# MM-Esp32S3.net
KiCad netlist of a schematic drawn in Altium Designer
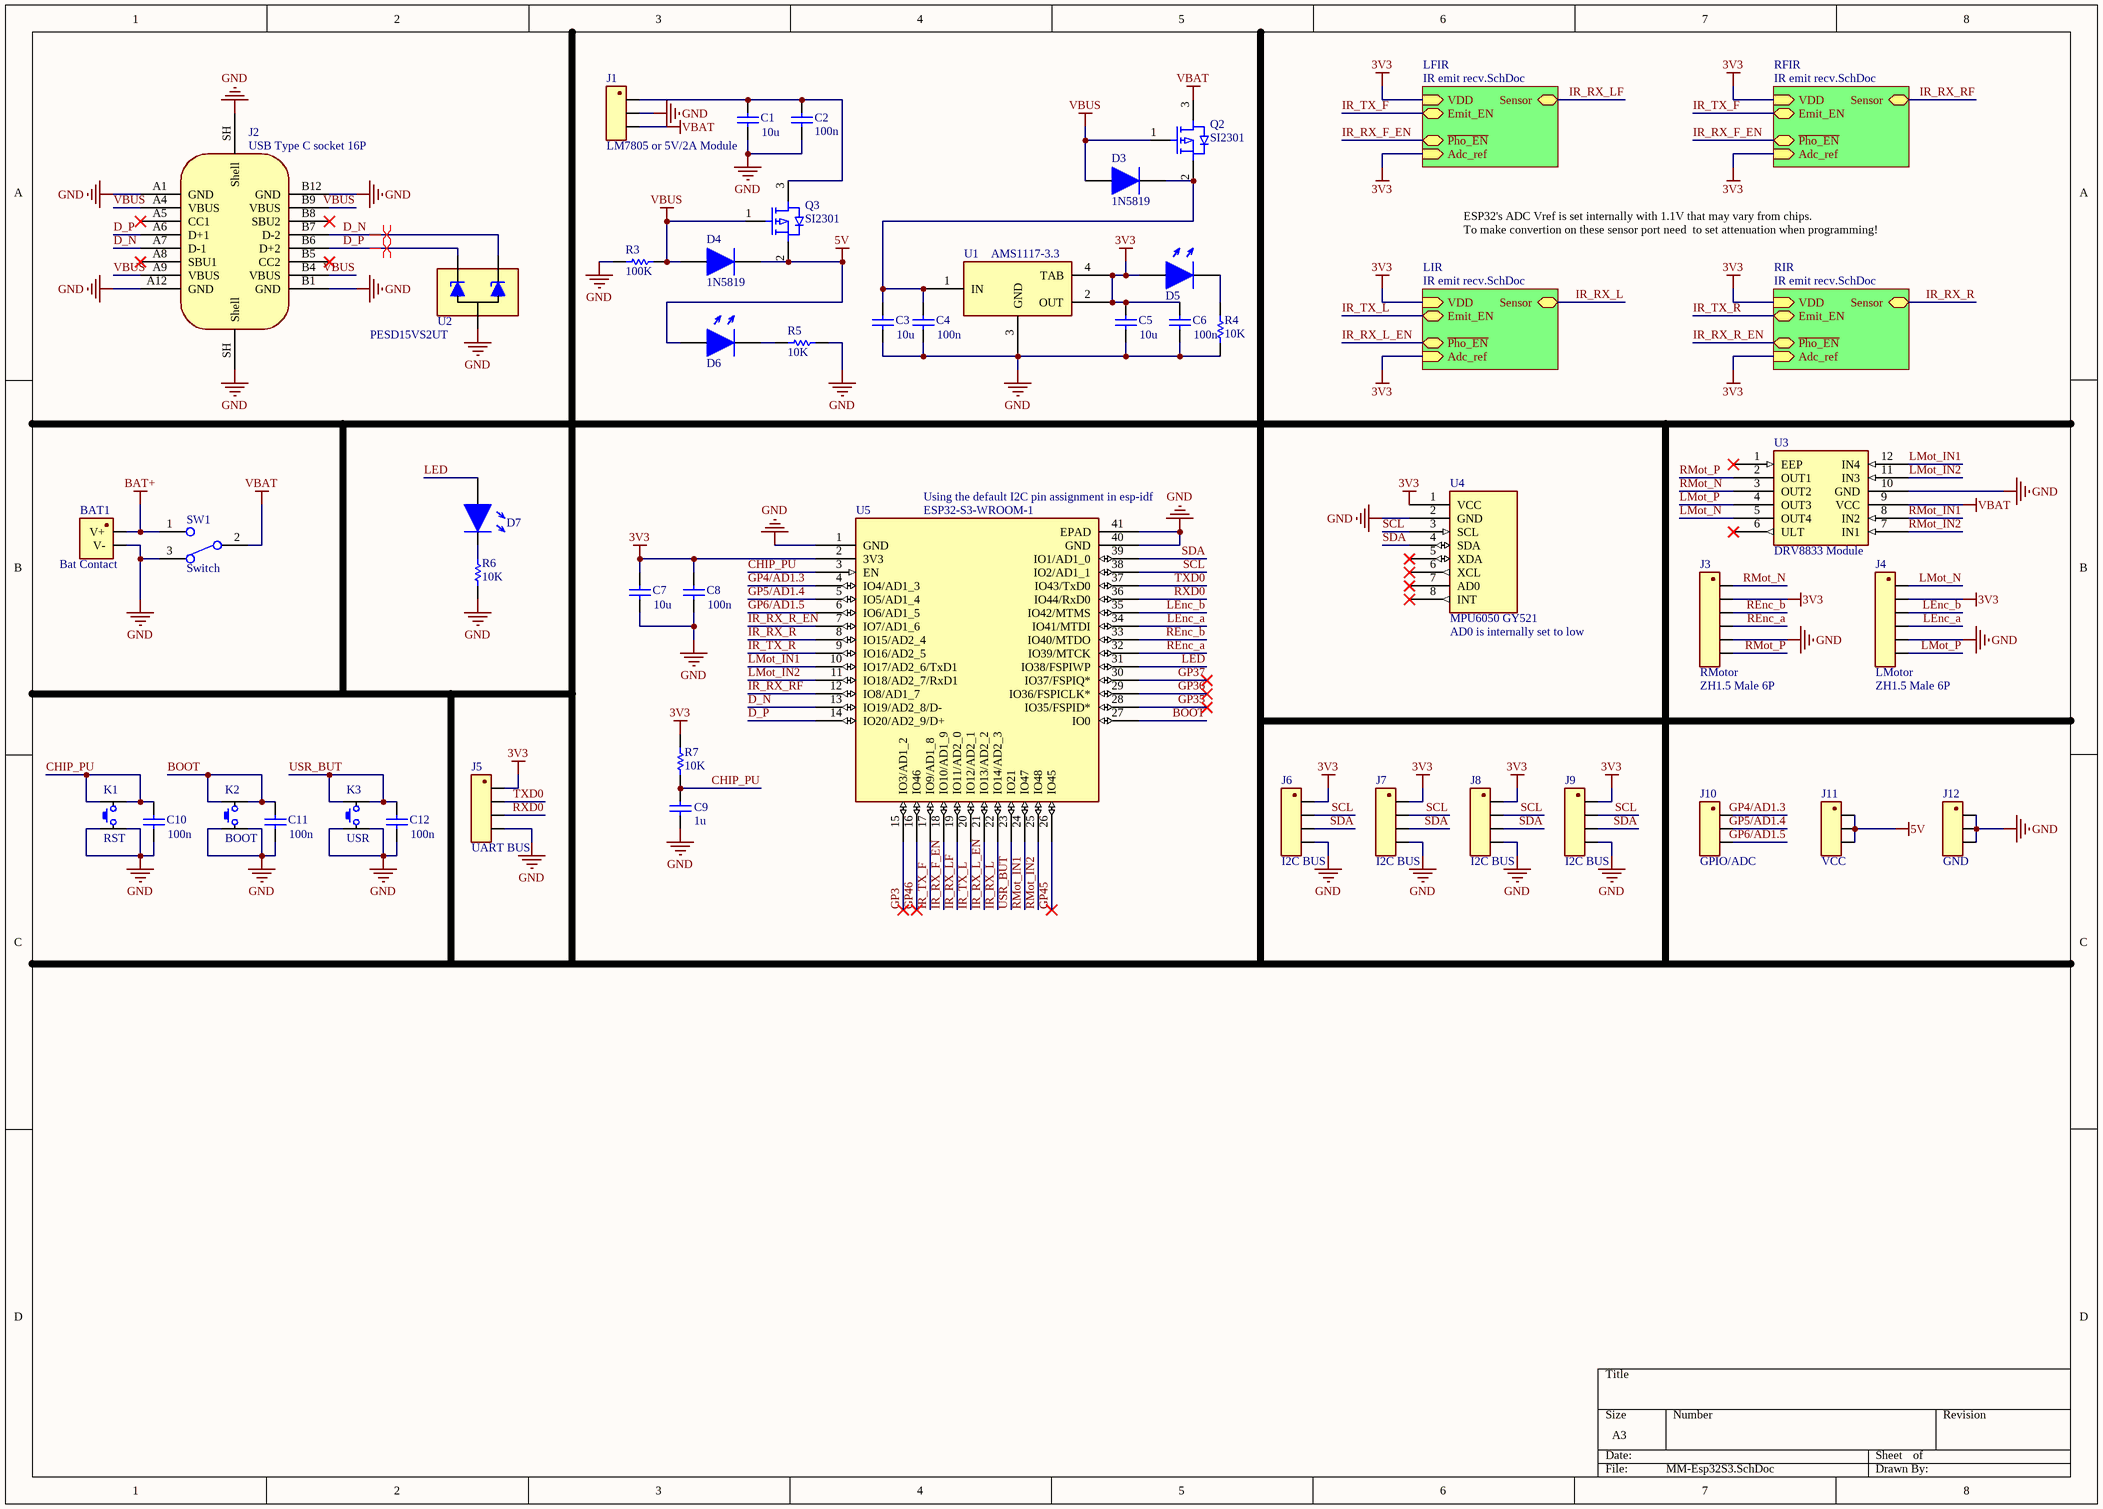
[diagram p0: MM-Esp32S3.SchDoc]

(export (version "E")
  (design (tool "Eeschema 10.0.6"))
  (components
    (comp (ref "BAT1")
      (value "Bat Contact")
      (footprint "9V BAT SNAP-ON 2 CONTACTS MF")
      (libsource (lib "My_Library") (part "Bat Contact"))
    )
    (comp (ref "C1")
      (value "10u")
      (footprint "0805 Cap")
      (description "无极电容")
      (fields (field (name "Comment") "Cap"))
      (libsource (lib "My_Library") (part "Cap"))
    )
    (comp (ref "C2")
      (value "100n")
      (footprint "0805 Cap")
      (description "无极电容")
      (fields (field (name "Comment") "Cap"))
      (libsource (lib "My_Library") (part "Cap"))
    )
    (comp (ref "C3")
      (value "10u")
      (footprint "0805 Cap")
      (description "无极电容")
      (fields (field (name "Comment") "Cap"))
      (libsource (lib "My_Library") (part "Cap"))
    )
    (comp (ref "C4")
      (value "100n")
      (footprint "0805 Cap")
      (description "无极电容")
      (fields (field (name "Comment") "Cap"))
      (libsource (lib "My_Library") (part "Cap"))
    )
    (comp (ref "C5")
      (value "10u")
      (footprint "0805 Cap")
      (description "无极电容")
      (fields (field (name "Comment") "Cap"))
      (libsource (lib "My_Library") (part "Cap"))
    )
    (comp (ref "C6")
      (value "100n")
      (footprint "0805 Cap")
      (description "无极电容")
      (fields (field (name "Comment") "Cap"))
      (libsource (lib "My_Library") (part "Cap"))
    )
    (comp (ref "C7")
      (value "10u")
      (footprint "0805 Cap")
      (description "无极电容")
      (fields (field (name "Comment") "Cap"))
      (libsource (lib "My_Library") (part "Cap"))
    )
    (comp (ref "C8")
      (value "100n")
      (footprint "0805 Cap")
      (description "无极电容")
      (fields (field (name "Comment") "Cap"))
      (libsource (lib "My_Library") (part "Cap"))
    )
    (comp (ref "C9")
      (value "1u")
      (footprint "0805 Cap")
      (description "无极电容")
      (fields (field (name "Comment") "Cap"))
      (libsource (lib "My_Library") (part "Cap"))
    )
    (comp (ref "C10")
      (value "100n")
      (footprint "0805 Cap")
      (description "无极电容")
      (fields (field (name "Comment") "Cap"))
      (libsource (lib "My_Library") (part "Cap"))
    )
    (comp (ref "C11")
      (value "100n")
      (footprint "0805 Cap")
      (description "无极电容")
      (fields (field (name "Comment") "Cap"))
      (libsource (lib "My_Library") (part "Cap"))
    )
    (comp (ref "C12")
      (value "100n")
      (footprint "0805 Cap")
      (description "无极电容")
      (fields (field (name "Comment") "Cap"))
      (libsource (lib "My_Library") (part "Cap"))
    )
    (comp (ref "D3") (value "1N5819") (footprint "SOD323 0805") (libsource (lib "My_Library") (part "Diode")))
    (comp (ref "D4") (value "1N5819") (footprint "SOD323 0805") (libsource (lib "My_Library") (part "Diode")))
    (comp (ref "D5")
      (value "LED")
      (footprint "LED 3mm")
      (description "发光二极管")
      (libsource (lib "My_Library") (part "LED"))
    )
    (comp (ref "D6")
      (value "LED")
      (footprint "LED 3mm")
      (description "发光二极管")
      (libsource (lib "My_Library") (part "LED"))
    )
    (comp (ref "D7")
      (value "LED")
      (footprint "LED 3mm")
      (description "发光二极管")
      (libsource (lib "My_Library") (part "LED"))
    )
    (comp (ref "J1")
      (value "LM7805 or 5V/2A Module")
      (footprint "Header 3Pins Female DIP")
      (libsource (lib "My_Library") (part "Header 3pin"))
    )
    (comp (ref "J2")
      (value "USB Type C socket 16P")
      (footprint "USB Type C 16P Through hole")
      (description "USB Type C母座 16P")
      (libsource (lib "My_Library") (part "USB Type C socket 16P"))
    )
    (comp (ref "J3")
      (value "RMotor")
      (footprint "ZH1.5 6PINS DIP")
      (fields (field (name "SIZE") "ZH1.5 Male 6P"))
      (libsource (lib "My_Library") (part "Header 6pin"))
    )
    (comp (ref "J4")
      (value "LMotor")
      (footprint "ZH1.5 6PINS DIP")
      (fields (field (name "SIZE") "ZH1.5 Male 6P"))
      (libsource (lib "My_Library") (part "Header 6pin"))
    )
    (comp (ref "J5")
      (value "UART BUS")
      (footprint "Header 4Pins DIP")
      (libsource (lib "My_Library") (part "Header 4pin"))
    )
    (comp (ref "J6")
      (value "I2C BUS")
      (footprint "Header 4Pins DIP")
      (libsource (lib "My_Library") (part "Header 4pin"))
    )
    (comp (ref "J7")
      (value "I2C BUS")
      (footprint "Header 4Pins DIP")
      (libsource (lib "My_Library") (part "Header 4pin"))
    )
    (comp (ref "J8")
      (value "I2C BUS")
      (footprint "Header 4Pins DIP")
      (libsource (lib "My_Library") (part "Header 4pin"))
    )
    (comp (ref "J9")
      (value "I2C BUS")
      (footprint "Header 4Pins DIP")
      (libsource (lib "My_Library") (part "Header 4pin"))
    )
    (comp (ref "J10")
      (value "GPIO/ADC")
      (footprint "Header 3Pins DIP")
      (libsource (lib "My_Library") (part "Header 3pin"))
    )
    (comp (ref "J11")
      (value "VCC")
      (footprint "Header 3Pins DIP")
      (libsource (lib "My_Library") (part "Header 3pin"))
    )
    (comp (ref "J12")
      (value "GND")
      (footprint "Header 3Pins DIP")
      (libsource (lib "My_Library") (part "Header 3pin"))
    )
    (comp (ref "K1")
      (value "RST")
      (footprint "BUTTON TH 6*6*5")
      (description "按键开关")
      (libsource (lib "My_Library") (part "Button"))
    )
    (comp (ref "K2")
      (value "BOOT")
      (footprint "BUTTON TH 6*6*5")
      (description "按键开关")
      (libsource (lib "My_Library") (part "Button"))
    )
    (comp (ref "K3")
      (value "USR")
      (footprint "BUTTON TH 6*6*5")
      (description "按键开关")
      (libsource (lib "My_Library") (part "Button"))
    )
    (comp (ref "Q2") (value "SI2301") (footprint "SOT23-3") (libsource (lib "My_Library") (part "PMOS")))
    (comp (ref "Q3") (value "SI2301") (footprint "SOT23-3") (libsource (lib "My_Library") (part "PMOS")))
    (comp (ref "R3")
      (value "100K")
      (footprint "0805 R/L")
      (fields (field (name "Comment") "Res"))
      (libsource (lib "My_Library") (part "Res"))
    )
    (comp (ref "R4")
      (value "10K")
      (footprint "0805 R/L")
      (fields (field (name "Comment") "Res"))
      (libsource (lib "My_Library") (part "Res"))
    )
    (comp (ref "R5")
      (value "10K")
      (footprint "0805 R/L")
      (fields (field (name "Comment") "Res"))
      (libsource (lib "My_Library") (part "Res"))
    )
    (comp (ref "R6")
      (value "10K")
      (footprint "0805 R/L")
      (fields (field (name "Comment") "Res"))
      (libsource (lib "My_Library") (part "Res"))
    )
    (comp (ref "R7")
      (value "10K")
      (footprint "0805 R/L")
      (fields (field (name "Comment") "Res"))
      (libsource (lib "My_Library") (part "Res"))
    )
    (comp (ref "SW1")
      (value "Switch")
      (footprint "Slide switch")
      (description "开关 拨动开关 滑动开关")
      (libsource (lib "My_Library") (part "Switch"))
    )
    (comp (ref "U1")
      (value "AMS1117-3.3")
      (footprint "SOT-223")
      (libsource (lib "My_Library") (part "AMS1117"))
    )
    (comp (ref "U2")
      (value "PESD15VS2UT")
      (footprint "SOT23-3")
      (description "静电放电(ESD)保护器件")
      (libsource (lib "My_Library") (part "PESD15VS2UT"))
    )
    (comp (ref "U3")
      (value "DRV8833 Module")
      (footprint "DRV8833 MODULE")
      (description "DRV8833两路电机驱动模块\r\nhttps://detail.tmall.com/item.htm?id=543193414673")
      (libsource (lib "My_Library") (part "DRV8833 Module"))
    )
    (comp (ref "U4")
      (value "MPU6050 GY521")
      (footprint "MPU6050 Module")
      (description "淘宝上最常用的8针脚MPU6050")
      (libsource (lib "My_Library") (part "MPU6050 GY521"))
    )
    (comp (ref "U5")
      (value "ESP32-S3-WROOM-1")
      (footprint "ESP32-WROOM")
      (description "乐鑫ESP32S3Wroom模组\r\n内置芯片为ESP32-S3R8的模组中,*管脚只能用于连至内部的OSPI PSRAM")
      (libsource (lib "My_Library") (part "ESP32-S3-WROOM-1"))
    )
  )
  (nets
    (net (code "1") (name "/BOOT") (class "Default")
      (node (ref "C11") (pin "2") (pintype "passive"))
      (node (ref "K2") (pin "1") (pintype "passive"))
      (node (ref "K2") (pin "2") (pintype "passive"))
      (node (ref "U5") (pin "27") (pinfunction "IO0_27") (pintype "bidirectional"))
    )
    (net (code "2") (name "/CHIP_PU") (class "Default")
      (node (ref "C10") (pin "2") (pintype "passive"))
      (node (ref "C9") (pin "2") (pintype "passive"))
      (node (ref "K1") (pin "1") (pintype "passive"))
      (node (ref "K1") (pin "2") (pintype "passive"))
      (node (ref "R7") (pin "2") (pintype "passive"))
      (node (ref "U5") (pin "3") (pinfunction "EN_3") (pintype "input"))
    )
    (net (code "3") (name "/D_N") (class "Default")
      (node (ref "J2") (pin "A7") (pinfunction "D-1_A7") (pintype "passive"))
      (node (ref "J2") (pin "B7") (pinfunction "D-2_B7") (pintype "passive"))
      (node (ref "U2") (pin "1") (pintype "passive"))
      (node (ref "U5") (pin "13") (pinfunction "IO19/AD2_8/D-_13") (pintype "bidirectional"))
    )
    (net (code "4") (name "/D_P") (class "Default")
      (node (ref "J2") (pin "A6") (pinfunction "D+1_A6") (pintype "passive"))
      (node (ref "J2") (pin "B6") (pinfunction "D+2_B6") (pintype "passive"))
      (node (ref "U2") (pin "2") (pintype "passive"))
      (node (ref "U5") (pin "14") (pinfunction "IO20/AD2_9/D+_14") (pintype "bidirectional"))
    )
    (net (code "5") (name "/GP3") (class "Default")
      (node (ref "U5") (pin "15") (pinfunction "IO3/AD1_2_15") (pintype "bidirectional+no_connect"))
    )
    (net (code "6") (name "/GP4{slash}AD1.3") (class "Default")
      (node (ref "J10") (pin "1") (pintype "passive"))
      (node (ref "U5") (pin "4") (pinfunction "IO4/AD1_3_4") (pintype "bidirectional"))
    )
    (net (code "7") (name "/GP5{slash}AD1.4") (class "Default")
      (node (ref "J10") (pin "2") (pintype "passive"))
      (node (ref "U5") (pin "5") (pinfunction "IO5/AD1_4_5") (pintype "bidirectional"))
    )
    (net (code "8") (name "/GP6{slash}AD1.5") (class "Default")
      (node (ref "J10") (pin "3") (pintype "passive"))
      (node (ref "U5") (pin "6") (pinfunction "IO6/AD1_5_6") (pintype "bidirectional"))
    )
    (net (code "9") (name "/GP35") (class "Default")
      (node (ref "U5") (pin "28") (pinfunction "IO35/FSPID*_28") (pintype "bidirectional+no_connect"))
    )
    (net (code "10") (name "/GP36") (class "Default")
      (node (ref "U5") (pin "29") (pinfunction "IO36/FSPICLK*_29") (pintype "bidirectional+no_connect"))
    )
    (net (code "11") (name "/GP37") (class "Default")
      (node (ref "U5") (pin "30") (pinfunction "IO37/FSPIQ*_30") (pintype "bidirectional+no_connect"))
    )
    (net (code "12") (name "/GP45") (class "Default")
      (node (ref "U5") (pin "26") (pinfunction "IO45_26") (pintype "bidirectional+no_connect"))
    )
    (net (code "13") (name "/GP46") (class "Default")
      (node (ref "U5") (pin "16") (pinfunction "IO46_16") (pintype "bidirectional+no_connect"))
    )
    (net (code "14") (name "/IR_RX_F_EN") (class "Default")
      (node (ref "U5") (pin "18") (pinfunction "IO10/AD1_9_18") (pintype "bidirectional"))
    )
    (net (code "15") (name "/IR_RX_L") (class "Default")
      (node (ref "U5") (pin "22") (pinfunction "IO14/AD2_3_22") (pintype "bidirectional"))
    )
    (net (code "16") (name "/IR_RX_LF") (class "Default")
      (node (ref "U5") (pin "19") (pinfunction "IO11/AD2_0_19") (pintype "bidirectional"))
    )
    (net (code "17") (name "/IR_RX_L_EN") (class "Default")
      (node (ref "U5") (pin "21") (pinfunction "IO13/AD2_2_21") (pintype "bidirectional"))
    )
    (net (code "18") (name "/IR_RX_R") (class "Default")
      (node (ref "U5") (pin "8") (pinfunction "IO15/AD2_4_8") (pintype "bidirectional"))
    )
    (net (code "19") (name "/IR_RX_RF") (class "Default")
      (node (ref "U5") (pin "12") (pinfunction "IO8/AD1_7_12") (pintype "bidirectional"))
    )
    (net (code "20") (name "/IR_RX_R_EN") (class "Default")
      (node (ref "U5") (pin "7") (pinfunction "IO7/AD1_6_7") (pintype "bidirectional"))
    )
    (net (code "21") (name "/IR_TX_F") (class "Default")
      (node (ref "U5") (pin "17") (pinfunction "IO9/AD1_8_17") (pintype "bidirectional"))
    )
    (net (code "22") (name "/IR_TX_L") (class "Default")
      (node (ref "U5") (pin "20") (pinfunction "IO12/AD2_1_20") (pintype "bidirectional"))
    )
    (net (code "23") (name "/IR_TX_R") (class "Default")
      (node (ref "U5") (pin "9") (pinfunction "IO16/AD2_5_9") (pintype "bidirectional"))
    )
    (net (code "24") (name "/LED") (class "Default")
      (node (ref "D7") (pin "2") (pintype "passive"))
      (node (ref "U5") (pin "31") (pinfunction "IO38/FSPIWP_31") (pintype "bidirectional"))
    )
    (net (code "25") (name "/LEnc_a") (class "Default")
      (node (ref "J4") (pin "4") (pintype "passive"))
      (node (ref "U5") (pin "34") (pinfunction "IO41/MTDI_34") (pintype "bidirectional"))
    )
    (net (code "26") (name "/LEnc_b") (class "Default")
      (node (ref "J4") (pin "3") (pintype "passive"))
      (node (ref "U5") (pin "35") (pinfunction "IO42/MTMS_35") (pintype "bidirectional"))
    )
    (net (code "27") (name "/LMot_IN1") (class "Default")
      (node (ref "U3") (pin "12") (pinfunction "IN4_12") (pintype "input"))
      (node (ref "U5") (pin "10") (pinfunction "IO17/AD2_6/TxD1_10") (pintype "bidirectional"))
    )
    (net (code "28") (name "/LMot_IN2") (class "Default")
      (node (ref "U3") (pin "11") (pinfunction "IN3_11") (pintype "input"))
      (node (ref "U5") (pin "11") (pinfunction "IO18/AD2_7/RxD1_11") (pintype "bidirectional"))
    )
    (net (code "29") (name "/LMot_N") (class "Default")
      (node (ref "J4") (pin "1") (pintype "passive"))
      (node (ref "U3") (pin "5") (pinfunction "OUT4_5") (pintype "passive"))
    )
    (net (code "30") (name "/LMot_P") (class "Default")
      (node (ref "J4") (pin "6") (pintype "passive"))
      (node (ref "U3") (pin "4") (pinfunction "OUT3_4") (pintype "passive"))
    )
    (net (code "31") (name "/REnc_a") (class "Default")
      (node (ref "J3") (pin "4") (pintype "passive"))
      (node (ref "U5") (pin "32") (pinfunction "IO39/MTCK_32") (pintype "bidirectional"))
    )
    (net (code "32") (name "/REnc_b") (class "Default")
      (node (ref "J3") (pin "3") (pintype "passive"))
      (node (ref "U5") (pin "33") (pinfunction "IO40/MTDO_33") (pintype "bidirectional"))
    )
    (net (code "33") (name "/RMot_IN1") (class "Default")
      (node (ref "U3") (pin "8") (pinfunction "IN2_8") (pintype "input"))
      (node (ref "U5") (pin "24") (pinfunction "IO47_24") (pintype "bidirectional"))
    )
    (net (code "34") (name "/RMot_IN2") (class "Default")
      (node (ref "U3") (pin "7") (pinfunction "IN1_7") (pintype "input"))
      (node (ref "U5") (pin "25") (pinfunction "IO48_25") (pintype "bidirectional"))
    )
    (net (code "35") (name "/RMot_N") (class "Default")
      (node (ref "J3") (pin "1") (pintype "passive"))
      (node (ref "U3") (pin "3") (pinfunction "OUT2_3") (pintype "passive"))
    )
    (net (code "36") (name "/RMot_P") (class "Default")
      (node (ref "J3") (pin "6") (pintype "passive"))
      (node (ref "U3") (pin "2") (pinfunction "OUT1_2") (pintype "power_in"))
    )
    (net (code "37") (name "/RXD0") (class "Default")
      (node (ref "J5") (pin "3") (pintype "passive"))
      (node (ref "U5") (pin "36") (pinfunction "IO44/RxD0_36") (pintype "bidirectional"))
    )
    (net (code "38") (name "/SCL") (class "Default")
      (node (ref "J6") (pin "2") (pintype "passive"))
      (node (ref "J7") (pin "2") (pintype "passive"))
      (node (ref "J8") (pin "2") (pintype "passive"))
      (node (ref "J9") (pin "2") (pintype "passive"))
      (node (ref "U4") (pin "3") (pinfunction "SCL_3") (pintype "input"))
      (node (ref "U5") (pin "38") (pinfunction "IO2/AD1_1_38") (pintype "bidirectional"))
    )
    (net (code "39") (name "/SDA") (class "Default")
      (node (ref "J6") (pin "3") (pintype "passive"))
      (node (ref "J7") (pin "3") (pintype "passive"))
      (node (ref "J8") (pin "3") (pintype "passive"))
      (node (ref "J9") (pin "3") (pintype "passive"))
      (node (ref "U4") (pin "4") (pinfunction "SDA_4") (pintype "bidirectional"))
      (node (ref "U5") (pin "39") (pinfunction "IO1/AD1_0_39") (pintype "bidirectional"))
    )
    (net (code "40") (name "/TXD0") (class "Default")
      (node (ref "J5") (pin "2") (pintype "passive"))
      (node (ref "U5") (pin "37") (pinfunction "IO43/TxD0_37") (pintype "bidirectional"))
    )
    (net (code "41") (name "/USR_BUT") (class "Default")
      (node (ref "C12") (pin "2") (pintype "passive"))
      (node (ref "K3") (pin "1") (pintype "passive"))
      (node (ref "K3") (pin "2") (pintype "passive"))
      (node (ref "U5") (pin "23") (pinfunction "IO21_23") (pintype "bidirectional"))
    )
    (net (code "42") (name "3V3") (class "Default")
      (node (ref "C5") (pin "2") (pintype "passive"))
      (node (ref "C6") (pin "2") (pintype "passive"))
      (node (ref "C7") (pin "2") (pintype "passive"))
      (node (ref "C8") (pin "2") (pintype "passive"))
      (node (ref "D5") (pin "2") (pintype "passive"))
      (node (ref "J3") (pin "2") (pintype "passive"))
      (node (ref "J4") (pin "2") (pintype "passive"))
      (node (ref "J5") (pin "1") (pintype "passive"))
      (node (ref "J6") (pin "1") (pintype "passive"))
      (node (ref "J7") (pin "1") (pintype "passive"))
      (node (ref "J8") (pin "1") (pintype "passive"))
      (node (ref "J9") (pin "1") (pintype "passive"))
      (node (ref "R7") (pin "1") (pintype "passive"))
      (node (ref "U1") (pin "2") (pinfunction "OUT_2") (pintype "power_in"))
      (node (ref "U1") (pin "4") (pinfunction "TAB_4") (pintype "passive"))
      (node (ref "U4") (pin "1") (pinfunction "VCC_1") (pintype "power_in"))
      (node (ref "U5") (pin "2") (pinfunction "3V3_2") (pintype "power_in"))
    )
    (net (code "43") (name "5V") (class "Default")
      (node (ref "D4") (pin "2") (pintype "passive"))
      (node (ref "D6") (pin "2") (pintype "passive"))
      (node (ref "J11") (pin "1") (pintype "passive"))
      (node (ref "J11") (pin "2") (pintype "passive"))
      (node (ref "J11") (pin "3") (pintype "passive"))
      (node (ref "Q3") (pin "2") (pinfunction "S_2") (pintype "passive"))
    )
    (net (code "44") (name "BAT+") (class "Default")
      (node (ref "BAT1") (pin "1") (pinfunction "V+_1") (pintype "passive"))
      (node (ref "SW1") (pin "1") (pintype "passive"))
    )
    (net (code "45") (name "GND") (class "Default")
      (node (ref "BAT1") (pin "2") (pinfunction "V-_2") (pintype "passive"))
      (node (ref "C1") (pin "1") (pintype "passive"))
      (node (ref "C10") (pin "1") (pintype "passive"))
      (node (ref "C11") (pin "1") (pintype "passive"))
      (node (ref "C12") (pin "1") (pintype "passive"))
      (node (ref "C2") (pin "1") (pintype "passive"))
      (node (ref "C3") (pin "1") (pintype "passive"))
      (node (ref "C4") (pin "1") (pintype "passive"))
      (node (ref "C5") (pin "1") (pintype "passive"))
      (node (ref "C6") (pin "1") (pintype "passive"))
      (node (ref "C7") (pin "1") (pintype "passive"))
      (node (ref "C8") (pin "1") (pintype "passive"))
      (node (ref "C9") (pin "1") (pintype "passive"))
      (node (ref "J1") (pin "2") (pintype "passive"))
      (node (ref "J12") (pin "1") (pintype "passive"))
      (node (ref "J12") (pin "2") (pintype "passive"))
      (node (ref "J12") (pin "3") (pintype "passive"))
      (node (ref "J2") (pin "A1") (pinfunction "GND_A1") (pintype "passive"))
      (node (ref "J2") (pin "A12") (pinfunction "GND_A12") (pintype "passive"))
      (node (ref "J2") (pin "B1") (pinfunction "GND_B1") (pintype "passive"))
      (node (ref "J2") (pin "B12") (pinfunction "GND_B12") (pintype "passive"))
      (node (ref "J2") (pin "SH") (pinfunction "Shell_SH") (pintype "passive"))
      (node (ref "J3") (pin "5") (pintype "passive"))
      (node (ref "J4") (pin "5") (pintype "passive"))
      (node (ref "J5") (pin "4") (pintype "passive"))
      (node (ref "J6") (pin "4") (pintype "passive"))
      (node (ref "J7") (pin "4") (pintype "passive"))
      (node (ref "J8") (pin "4") (pintype "passive"))
      (node (ref "J9") (pin "4") (pintype "passive"))
      (node (ref "K1") (pin "3") (pintype "passive"))
      (node (ref "K1") (pin "4") (pintype "passive"))
      (node (ref "K2") (pin "3") (pintype "passive"))
      (node (ref "K2") (pin "4") (pintype "passive"))
      (node (ref "K3") (pin "3") (pintype "passive"))
      (node (ref "K3") (pin "4") (pintype "passive"))
      (node (ref "R3") (pin "2") (pintype "passive"))
      (node (ref "R4") (pin "2") (pintype "passive"))
      (node (ref "R5") (pin "2") (pintype "passive"))
      (node (ref "R6") (pin "2") (pintype "passive"))
      (node (ref "SW1") (pin "3") (pintype "passive"))
      (node (ref "U1") (pin "3") (pinfunction "GND_3") (pintype "power_in"))
      (node (ref "U2") (pin "3") (pintype "passive"))
      (node (ref "U3") (pin "10") (pinfunction "GND_10") (pintype "passive"))
      (node (ref "U4") (pin "2") (pinfunction "GND_2") (pintype "power_in"))
      (node (ref "U5") (pin "1") (pinfunction "GND_1") (pintype "power_in"))
      (node (ref "U5") (pin "40") (pinfunction "GND_40") (pintype "power_in"))
      (node (ref "U5") (pin "41") (pinfunction "EPAD_41") (pintype "power_in"))
    )
    (net (code "46") (name "Net-(D5-Pad1)") (class "Default")
      (node (ref "D5") (pin "1") (pintype "passive"))
      (node (ref "R4") (pin "1") (pintype "passive"))
    )
    (net (code "47") (name "Net-(D6-Pad1)") (class "Default")
      (node (ref "D6") (pin "1") (pintype "passive"))
      (node (ref "R5") (pin "1") (pintype "passive"))
    )
    (net (code "48") (name "Net-(D7-Pad1)") (class "Default")
      (node (ref "D7") (pin "1") (pintype "passive"))
      (node (ref "R6") (pin "1") (pintype "passive"))
    )
    (net (code "49") (name "Net-(Q2-S)") (class "Default")
      (node (ref "C3") (pin "2") (pintype "passive"))
      (node (ref "C4") (pin "2") (pintype "passive"))
      (node (ref "D3") (pin "2") (pintype "passive"))
      (node (ref "Q2") (pin "2") (pinfunction "S_2") (pintype "passive"))
      (node (ref "U1") (pin "1") (pinfunction "IN_1") (pintype "power_in"))
    )
    (net (code "50") (name "Net-(Q3-D)") (class "Default")
      (node (ref "C1") (pin "2") (pintype "passive"))
      (node (ref "C2") (pin "2") (pintype "passive"))
      (node (ref "J1") (pin "1") (pintype "passive"))
      (node (ref "Q3") (pin "3") (pinfunction "D_3") (pintype "passive"))
    )
    (net (code "51") (name "VBAT") (class "Default")
      (node (ref "J1") (pin "3") (pintype "passive"))
      (node (ref "Q2") (pin "3") (pinfunction "D_3") (pintype "passive"))
      (node (ref "SW1") (pin "2") (pintype "passive"))
      (node (ref "U3") (pin "9") (pinfunction "VCC_9") (pintype "passive"))
    )
    (net (code "52") (name "VBUS") (class "Default")
      (node (ref "D3") (pin "1") (pintype "passive"))
      (node (ref "D4") (pin "1") (pintype "passive"))
      (node (ref "J2") (pin "A4") (pinfunction "VBUS_A4") (pintype "passive"))
      (node (ref "J2") (pin "A9") (pinfunction "VBUS_A9") (pintype "passive"))
      (node (ref "J2") (pin "B4") (pinfunction "VBUS_B4") (pintype "passive"))
      (node (ref "J2") (pin "B9") (pinfunction "VBUS_B9") (pintype "passive"))
      (node (ref "Q2") (pin "1") (pinfunction "G_1") (pintype "passive"))
      (node (ref "Q3") (pin "1") (pinfunction "G_1") (pintype "passive"))
      (node (ref "R3") (pin "1") (pintype "passive"))
    )
    (net (code "53") (name "unconnected-(J2-CC1-PadA5)") (class "Default")
      (node (ref "J2") (pin "A5") (pinfunction "CC1_A5") (pintype "passive+no_connect"))
    )
    (net (code "54") (name "unconnected-(J2-CC2-PadB5)") (class "Default")
      (node (ref "J2") (pin "B5") (pinfunction "CC2_B5") (pintype "passive+no_connect"))
    )
    (net (code "55") (name "unconnected-(J2-SBU1-PadA8)") (class "Default")
      (node (ref "J2") (pin "A8") (pinfunction "SBU1_A8") (pintype "passive+no_connect"))
    )
    (net (code "56") (name "unconnected-(J2-SBU2-PadB8)") (class "Default")
      (node (ref "J2") (pin "B8") (pinfunction "SBU2_B8") (pintype "passive+no_connect"))
    )
    (net (code "57") (name "unconnected-(U3-EEP-Pad1)") (class "Default")
      (node (ref "U3") (pin "1") (pinfunction "EEP_1") (pintype "input+no_connect"))
    )
    (net (code "58") (name "unconnected-(U3-ULT-Pad6)") (class "Default")
      (node (ref "U3") (pin "6") (pinfunction "ULT_6") (pintype "output+no_connect"))
    )
    (net (code "59") (name "unconnected-(U4-AD0-Pad7)") (class "Default")
      (node (ref "U4") (pin "7") (pinfunction "AD0_7") (pintype "power_in+no_connect"))
    )
    (net (code "60") (name "unconnected-(U4-INT-Pad8)") (class "Default")
      (node (ref "U4") (pin "8") (pinfunction "INT_8") (pintype "output+no_connect"))
    )
    (net (code "61") (name "unconnected-(U4-XCL-Pad6)") (class "Default")
      (node (ref "U4") (pin "6") (pinfunction "XCL_6") (pintype "output+no_connect"))
    )
    (net (code "62") (name "unconnected-(U4-XDA-Pad5)") (class "Default")
      (node (ref "U4") (pin "5") (pinfunction "XDA_5") (pintype "bidirectional+no_connect"))
    )
  )
)
